# Backplane_Breakout_Adapter_Connectors.net
KiCad netlist of a schematic drawn in Altium Designer
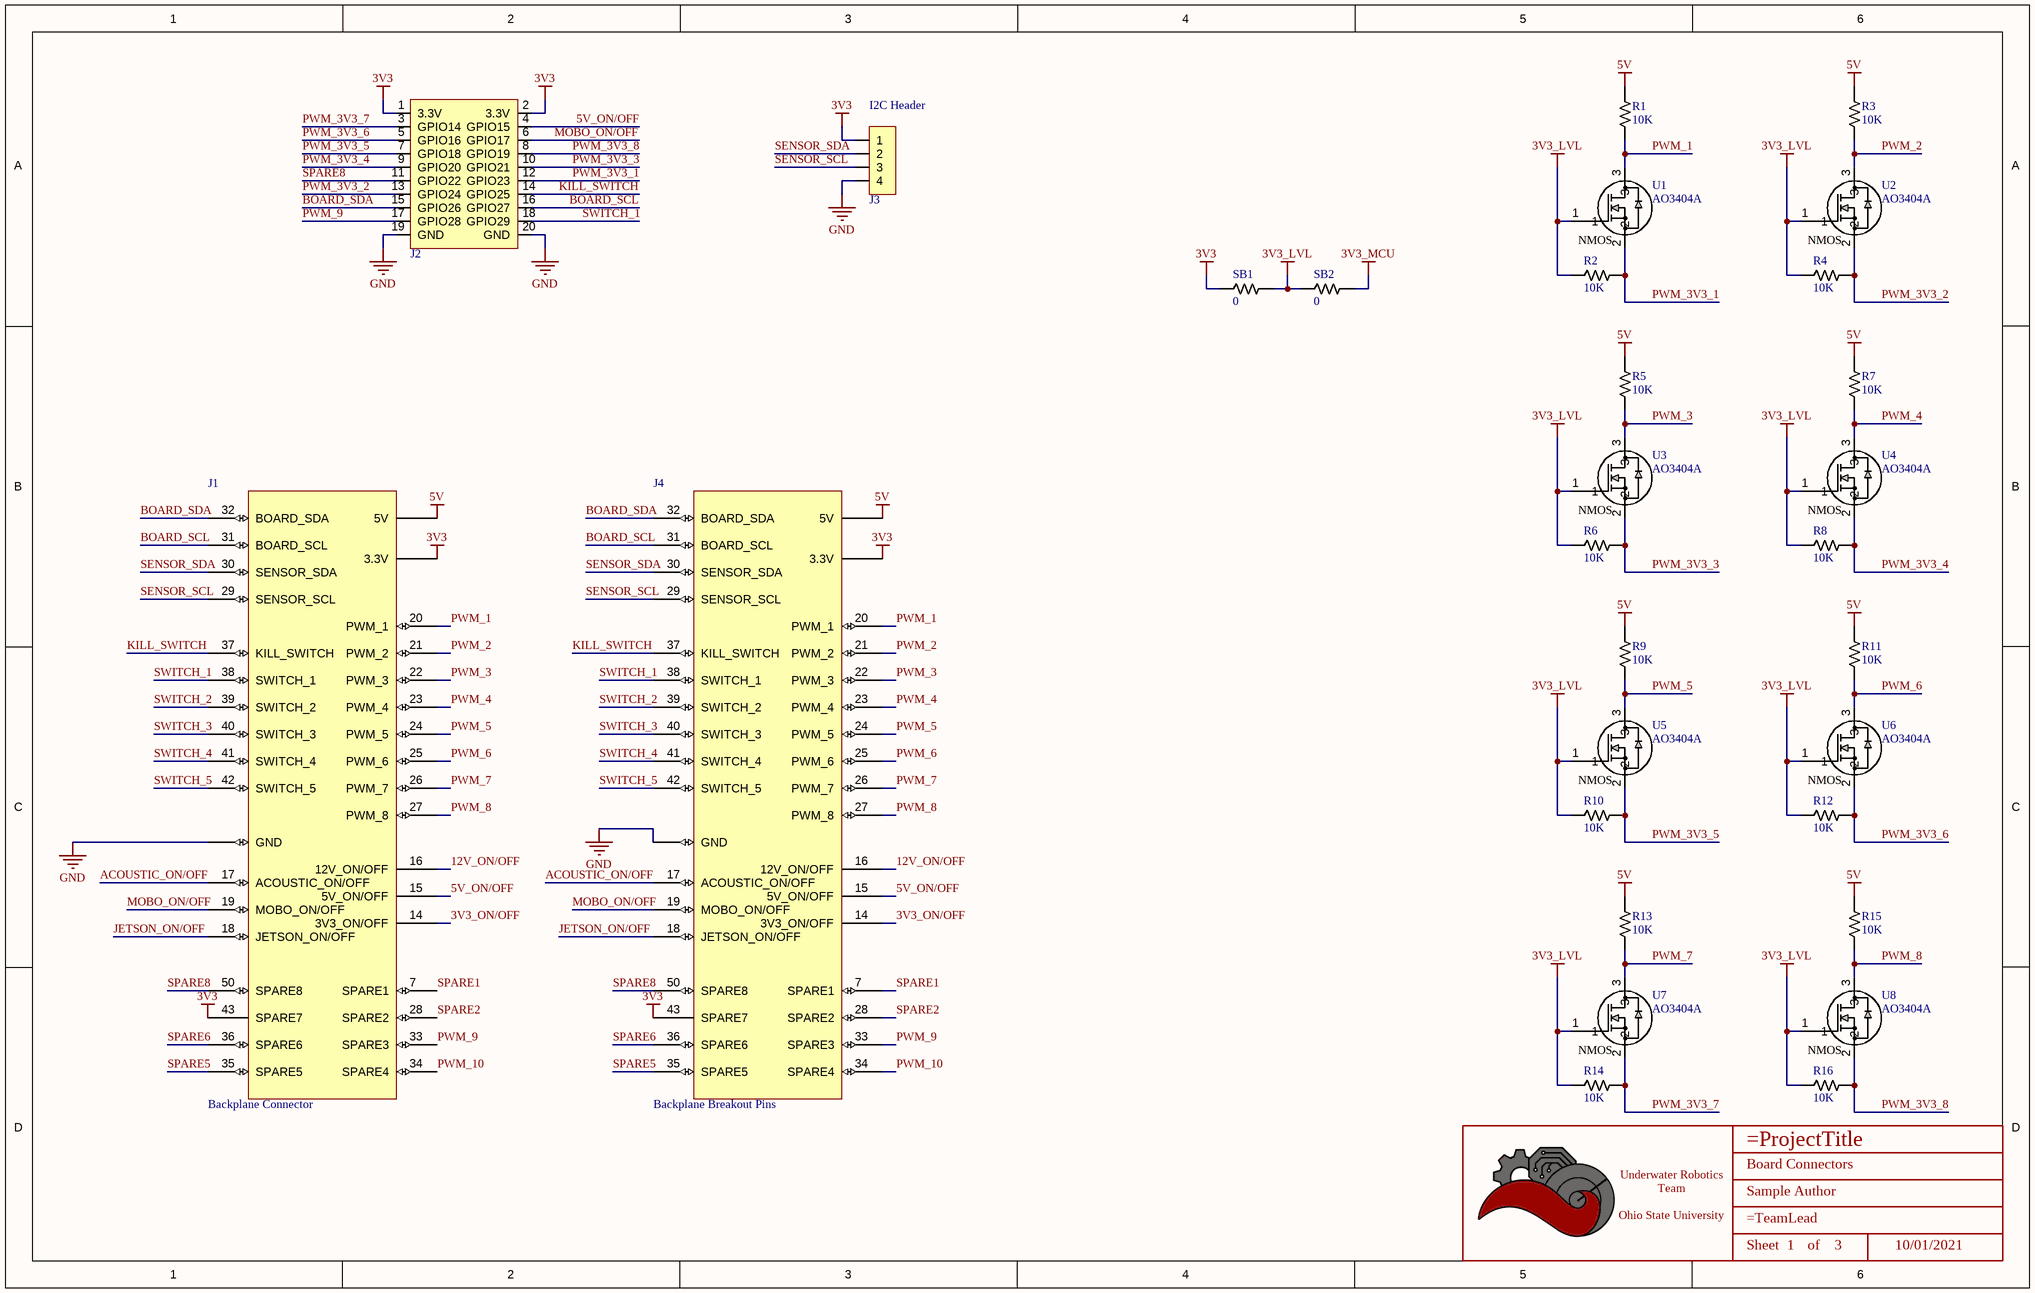
[diagram p0: Backplane_Breakout_Adapter_Connectors.SchDoc]

(export (version "E")
  (design (tool "Eeschema 10.0.6"))
  (components
    (comp (ref "*")
      (value "Title_Block")
      (footprint "LOGO")
      (description "UWRT Schematic Title Block Template\r\n\r\nCreated June 2021, Dylan Trainor")
      (libsource (lib "UWRT") (part "Title_Block"))
    )
    (comp (ref "J1")
      (value "Backplane Connector")
      (footprint "BACKPLANE_EDGE_CONN")
      (description "Titan Backplane Edge Connector")
      (libsource (lib "Connectors") (part "BACKBOARD_EDGE_CONN"))
    )
    (comp (ref "J2")
      (value "RP2040 GPIO Header")
      (footprint "HEADER_MIRRORED_2x10PIN_2.54MM")
      (description "CONN HEADER VERT 20POS 2.54MM")
      (fields (field (name "MADE BY") "Robert Pafford"))
      (libsource (lib "Connectors") (part "HEADER_2x10PIN_2.54MM_RP2040_GPIO"))
    )
    (comp (ref "J3")
      (value "CONN HEADER VERT 4POS 2.54MM")
      (footprint "HEADER_MIRRORED_4PIN_2.54MM")
      (fields (field (name "MADE BY") "Robert Pafford"))
      (libsource (lib "Connectors") (part "HEADER_4PIN_2.54MM"))
    )
    (comp (ref "J4")
      (value "Backplane Breakout Pins")
      (footprint "HEADER_2X28PIN_2.54MM")
      (description "Titan Backplane Edge Connector")
      (libsource (lib "Connectors") (part "BACKBOARD_EDGE_CONN"))
    )
    (comp (ref "R1")
      (value "10k Ohm 5% 1/10W")
      (footprint "RESISTOR_0603")
      (description "RES 10k OHM 5% 1/10W 0603")
      (fields
        (field (name "TOLERANCE") "+/- 5%")
        (field (name "VALUE  (OHMS)") "10K")
        (field (name "MADE BY") "Robert Pafford")
      )
      (libsource (lib "Resistors") (part "RESISTOR_10K_0603"))
    )
    (comp (ref "R2")
      (value "10k Ohm 5% 1/10W")
      (footprint "RESISTOR_0603")
      (description "RES 10k OHM 5% 1/10W 0603")
      (fields
        (field (name "TOLERANCE") "+/- 5%")
        (field (name "VALUE  (OHMS)") "10K")
        (field (name "MADE BY") "Robert Pafford")
      )
      (libsource (lib "Resistors") (part "RESISTOR_10K_0603"))
    )
    (comp (ref "R3")
      (value "10k Ohm 5% 1/10W")
      (footprint "RESISTOR_0603")
      (description "RES 10k OHM 5% 1/10W 0603")
      (fields
        (field (name "TOLERANCE") "+/- 5%")
        (field (name "VALUE  (OHMS)") "10K")
        (field (name "MADE BY") "Robert Pafford")
      )
      (libsource (lib "Resistors") (part "RESISTOR_10K_0603"))
    )
    (comp (ref "R4")
      (value "10k Ohm 5% 1/10W")
      (footprint "RESISTOR_0603")
      (description "RES 10k OHM 5% 1/10W 0603")
      (fields
        (field (name "TOLERANCE") "+/- 5%")
        (field (name "VALUE  (OHMS)") "10K")
        (field (name "MADE BY") "Robert Pafford")
      )
      (libsource (lib "Resistors") (part "RESISTOR_10K_0603"))
    )
    (comp (ref "R5")
      (value "10k Ohm 5% 1/10W")
      (footprint "RESISTOR_0603")
      (description "RES 10k OHM 5% 1/10W 0603")
      (fields
        (field (name "TOLERANCE") "+/- 5%")
        (field (name "VALUE  (OHMS)") "10K")
        (field (name "MADE BY") "Robert Pafford")
      )
      (libsource (lib "Resistors") (part "RESISTOR_10K_0603"))
    )
    (comp (ref "R6")
      (value "10k Ohm 5% 1/10W")
      (footprint "RESISTOR_0603")
      (description "RES 10k OHM 5% 1/10W 0603")
      (fields
        (field (name "TOLERANCE") "+/- 5%")
        (field (name "VALUE  (OHMS)") "10K")
        (field (name "MADE BY") "Robert Pafford")
      )
      (libsource (lib "Resistors") (part "RESISTOR_10K_0603"))
    )
    (comp (ref "R7")
      (value "10k Ohm 5% 1/10W")
      (footprint "RESISTOR_0603")
      (description "RES 10k OHM 5% 1/10W 0603")
      (fields
        (field (name "TOLERANCE") "+/- 5%")
        (field (name "VALUE  (OHMS)") "10K")
        (field (name "MADE BY") "Robert Pafford")
      )
      (libsource (lib "Resistors") (part "RESISTOR_10K_0603"))
    )
    (comp (ref "R8")
      (value "10k Ohm 5% 1/10W")
      (footprint "RESISTOR_0603")
      (description "RES 10k OHM 5% 1/10W 0603")
      (fields
        (field (name "TOLERANCE") "+/- 5%")
        (field (name "VALUE  (OHMS)") "10K")
        (field (name "MADE BY") "Robert Pafford")
      )
      (libsource (lib "Resistors") (part "RESISTOR_10K_0603"))
    )
    (comp (ref "R9")
      (value "10k Ohm 5% 1/10W")
      (footprint "RESISTOR_0603")
      (description "RES 10k OHM 5% 1/10W 0603")
      (fields
        (field (name "TOLERANCE") "+/- 5%")
        (field (name "VALUE  (OHMS)") "10K")
        (field (name "MADE BY") "Robert Pafford")
      )
      (libsource (lib "Resistors") (part "RESISTOR_10K_0603"))
    )
    (comp (ref "R10")
      (value "10k Ohm 5% 1/10W")
      (footprint "RESISTOR_0603")
      (description "RES 10k OHM 5% 1/10W 0603")
      (fields
        (field (name "TOLERANCE") "+/- 5%")
        (field (name "VALUE  (OHMS)") "10K")
        (field (name "MADE BY") "Robert Pafford")
      )
      (libsource (lib "Resistors") (part "RESISTOR_10K_0603"))
    )
    (comp (ref "R11")
      (value "10k Ohm 5% 1/10W")
      (footprint "RESISTOR_0603")
      (description "RES 10k OHM 5% 1/10W 0603")
      (fields
        (field (name "TOLERANCE") "+/- 5%")
        (field (name "VALUE  (OHMS)") "10K")
        (field (name "MADE BY") "Robert Pafford")
      )
      (libsource (lib "Resistors") (part "RESISTOR_10K_0603"))
    )
    (comp (ref "R12")
      (value "10k Ohm 5% 1/10W")
      (footprint "RESISTOR_0603")
      (description "RES 10k OHM 5% 1/10W 0603")
      (fields
        (field (name "TOLERANCE") "+/- 5%")
        (field (name "VALUE  (OHMS)") "10K")
        (field (name "MADE BY") "Robert Pafford")
      )
      (libsource (lib "Resistors") (part "RESISTOR_10K_0603"))
    )
    (comp (ref "R13")
      (value "10k Ohm 5% 1/10W")
      (footprint "RESISTOR_0603")
      (description "RES 10k OHM 5% 1/10W 0603")
      (fields
        (field (name "TOLERANCE") "+/- 5%")
        (field (name "VALUE  (OHMS)") "10K")
        (field (name "MADE BY") "Robert Pafford")
      )
      (libsource (lib "Resistors") (part "RESISTOR_10K_0603"))
    )
    (comp (ref "R14")
      (value "10k Ohm 5% 1/10W")
      (footprint "RESISTOR_0603")
      (description "RES 10k OHM 5% 1/10W 0603")
      (fields
        (field (name "TOLERANCE") "+/- 5%")
        (field (name "VALUE  (OHMS)") "10K")
        (field (name "MADE BY") "Robert Pafford")
      )
      (libsource (lib "Resistors") (part "RESISTOR_10K_0603"))
    )
    (comp (ref "R15")
      (value "10k Ohm 5% 1/10W")
      (footprint "RESISTOR_0603")
      (description "RES 10k OHM 5% 1/10W 0603")
      (fields
        (field (name "TOLERANCE") "+/- 5%")
        (field (name "VALUE  (OHMS)") "10K")
        (field (name "MADE BY") "Robert Pafford")
      )
      (libsource (lib "Resistors") (part "RESISTOR_10K_0603"))
    )
    (comp (ref "R16")
      (value "10k Ohm 5% 1/10W")
      (footprint "RESISTOR_0603")
      (description "RES 10k OHM 5% 1/10W 0603")
      (fields
        (field (name "TOLERANCE") "+/- 5%")
        (field (name "VALUE  (OHMS)") "10K")
        (field (name "MADE BY") "Robert Pafford")
      )
      (libsource (lib "Resistors") (part "RESISTOR_10K_0603"))
    )
    (comp (ref "SB1")
      (value "0 Ohm Jumper No Fit")
      (footprint "RESISTOR_0603")
      (description "0 Ohm Jumper No Fit for Solder Bridge")
      (fields (field (name "VALUE  (OHMS)") "0") (field (name "MADE BY") "Robert Pafford"))
      (libsource (lib "Resistors") (part "JUMPER_0_0603"))
    )
    (comp (ref "SB2")
      (value "0 Ohm Jumper No Fit")
      (footprint "RESISTOR_0603")
      (description "0 Ohm Jumper No Fit for Solder Bridge")
      (fields (field (name "VALUE  (OHMS)") "0") (field (name "MADE BY") "Robert Pafford"))
      (libsource (lib "Resistors") (part "JUMPER_0_0603"))
    )
    (comp (ref "U1")
      (value "AO3404A")
      (footprint "SOT-23-3")
      (description "N-Channel 30 V 5.8A (Ta) 1.4W (Ta) Surface Mount SOT-23-3")
      (fields (field (name "CREATED BY") "Dylan T"))
      (libsource (lib "Transistors") (part "AO3404A"))
    )
    (comp (ref "U2")
      (value "AO3404A")
      (footprint "SOT-23-3")
      (description "N-Channel 30 V 5.8A (Ta) 1.4W (Ta) Surface Mount SOT-23-3")
      (fields (field (name "CREATED BY") "Dylan T"))
      (libsource (lib "Transistors") (part "AO3404A"))
    )
    (comp (ref "U3")
      (value "AO3404A")
      (footprint "SOT-23-3")
      (description "N-Channel 30 V 5.8A (Ta) 1.4W (Ta) Surface Mount SOT-23-3")
      (fields (field (name "CREATED BY") "Dylan T"))
      (libsource (lib "Transistors") (part "AO3404A"))
    )
    (comp (ref "U4")
      (value "AO3404A")
      (footprint "SOT-23-3")
      (description "N-Channel 30 V 5.8A (Ta) 1.4W (Ta) Surface Mount SOT-23-3")
      (fields (field (name "CREATED BY") "Dylan T"))
      (libsource (lib "Transistors") (part "AO3404A"))
    )
    (comp (ref "U5")
      (value "AO3404A")
      (footprint "SOT-23-3")
      (description "N-Channel 30 V 5.8A (Ta) 1.4W (Ta) Surface Mount SOT-23-3")
      (fields (field (name "CREATED BY") "Dylan T"))
      (libsource (lib "Transistors") (part "AO3404A"))
    )
    (comp (ref "U6")
      (value "AO3404A")
      (footprint "SOT-23-3")
      (description "N-Channel 30 V 5.8A (Ta) 1.4W (Ta) Surface Mount SOT-23-3")
      (fields (field (name "CREATED BY") "Dylan T"))
      (libsource (lib "Transistors") (part "AO3404A"))
    )
    (comp (ref "U7")
      (value "AO3404A")
      (footprint "SOT-23-3")
      (description "N-Channel 30 V 5.8A (Ta) 1.4W (Ta) Surface Mount SOT-23-3")
      (fields (field (name "CREATED BY") "Dylan T"))
      (libsource (lib "Transistors") (part "AO3404A"))
    )
    (comp (ref "U8")
      (value "AO3404A")
      (footprint "SOT-23-3")
      (description "N-Channel 30 V 5.8A (Ta) 1.4W (Ta) Surface Mount SOT-23-3")
      (fields (field (name "CREATED BY") "Dylan T"))
      (libsource (lib "Transistors") (part "AO3404A"))
    )
  )
  (nets
    (net (code "1") (name "/3V3_ON{slash}OFF") (class "Default")
      (node (ref "J1") (pin "14") (pinfunction "3V3_ON/OFF_14") (pintype "power_in"))
      (node (ref "J4") (pin "14") (pinfunction "3V3_ON/OFF_14") (pintype "power_in"))
    )
    (net (code "2") (name "/5V_ON{slash}OFF") (class "Default")
      (node (ref "J1") (pin "15") (pinfunction "5V_ON/OFF_15") (pintype "power_in"))
      (node (ref "J2") (pin "4") (pinfunction "GPIO15_4") (pintype "bidirectional"))
      (node (ref "J4") (pin "15") (pinfunction "5V_ON/OFF_15") (pintype "power_in"))
    )
    (net (code "3") (name "/12V_ON{slash}OFF") (class "Default")
      (node (ref "J1") (pin "16") (pinfunction "12V_ON/OFF_16") (pintype "power_in"))
      (node (ref "J4") (pin "16") (pinfunction "12V_ON/OFF_16") (pintype "power_in"))
    )
    (net (code "4") (name "/ACOUSTIC_ON{slash}OFF") (class "Default")
      (node (ref "J1") (pin "17") (pinfunction "ACOUSTIC_ON/OFF_17") (pintype "bidirectional"))
      (node (ref "J4") (pin "17") (pinfunction "ACOUSTIC_ON/OFF_17") (pintype "bidirectional"))
    )
    (net (code "5") (name "/BOARD_SCL") (class "Default")
      (node (ref "J1") (pin "31") (pinfunction "BOARD_SCL_31") (pintype "bidirectional"))
      (node (ref "J2") (pin "16") (pinfunction "GPIO27_16") (pintype "bidirectional"))
      (node (ref "J4") (pin "31") (pinfunction "BOARD_SCL_31") (pintype "bidirectional"))
    )
    (net (code "6") (name "/BOARD_SDA") (class "Default")
      (node (ref "J1") (pin "32") (pinfunction "BOARD_SDA_32") (pintype "bidirectional"))
      (node (ref "J2") (pin "15") (pinfunction "GPIO26_15") (pintype "bidirectional"))
      (node (ref "J4") (pin "32") (pinfunction "BOARD_SDA_32") (pintype "bidirectional"))
    )
    (net (code "7") (name "/JETSON_ON{slash}OFF") (class "Default")
      (node (ref "J1") (pin "18") (pinfunction "JETSON_ON/OFF_18") (pintype "bidirectional"))
      (node (ref "J4") (pin "18") (pinfunction "JETSON_ON/OFF_18") (pintype "bidirectional"))
    )
    (net (code "8") (name "/KILL_SWITCH") (class "Default")
      (node (ref "J1") (pin "37") (pinfunction "KILL_SWITCH_37") (pintype "bidirectional"))
      (node (ref "J2") (pin "14") (pinfunction "GPIO25_14") (pintype "bidirectional"))
      (node (ref "J4") (pin "37") (pinfunction "KILL_SWITCH_37") (pintype "bidirectional"))
    )
    (net (code "9") (name "/MOBO_ON{slash}OFF") (class "Default")
      (node (ref "J1") (pin "19") (pinfunction "MOBO_ON/OFF_19") (pintype "bidirectional"))
      (node (ref "J2") (pin "6") (pinfunction "GPIO17_6") (pintype "bidirectional"))
      (node (ref "J4") (pin "19") (pinfunction "MOBO_ON/OFF_19") (pintype "bidirectional"))
    )
    (net (code "10") (name "/PWM_1") (class "Default")
      (node (ref "J1") (pin "20") (pinfunction "PWM_1_20") (pintype "bidirectional"))
      (node (ref "J4") (pin "20") (pinfunction "PWM_1_20") (pintype "bidirectional"))
      (node (ref "R1") (pin "2") (pinfunction "2_2") (pintype "passive"))
      (node (ref "U1") (pin "3") (pinfunction "3_3") (pintype "passive"))
    )
    (net (code "11") (name "/PWM_2") (class "Default")
      (node (ref "J1") (pin "21") (pinfunction "PWM_2_21") (pintype "bidirectional"))
      (node (ref "J4") (pin "21") (pinfunction "PWM_2_21") (pintype "bidirectional"))
      (node (ref "R3") (pin "2") (pinfunction "2_2") (pintype "passive"))
      (node (ref "U2") (pin "3") (pinfunction "3_3") (pintype "passive"))
    )
    (net (code "12") (name "/PWM_3") (class "Default")
      (node (ref "J1") (pin "22") (pinfunction "PWM_3_22") (pintype "bidirectional"))
      (node (ref "J4") (pin "22") (pinfunction "PWM_3_22") (pintype "bidirectional"))
      (node (ref "R5") (pin "2") (pinfunction "2_2") (pintype "passive"))
      (node (ref "U3") (pin "3") (pinfunction "3_3") (pintype "passive"))
    )
    (net (code "13") (name "/PWM_3V3_1") (class "Default")
      (node (ref "J2") (pin "12") (pinfunction "GPIO23_12") (pintype "bidirectional"))
      (node (ref "R2") (pin "1") (pinfunction "1_1") (pintype "passive"))
      (node (ref "U1") (pin "2") (pinfunction "2_2") (pintype "passive"))
    )
    (net (code "14") (name "/PWM_3V3_2") (class "Default")
      (node (ref "J2") (pin "13") (pinfunction "GPIO24_13") (pintype "bidirectional"))
      (node (ref "R4") (pin "1") (pinfunction "1_1") (pintype "passive"))
      (node (ref "U2") (pin "2") (pinfunction "2_2") (pintype "passive"))
    )
    (net (code "15") (name "/PWM_3V3_3") (class "Default")
      (node (ref "J2") (pin "10") (pinfunction "GPIO21_10") (pintype "bidirectional"))
      (node (ref "R6") (pin "1") (pinfunction "1_1") (pintype "passive"))
      (node (ref "U3") (pin "2") (pinfunction "2_2") (pintype "passive"))
    )
    (net (code "16") (name "/PWM_3V3_4") (class "Default")
      (node (ref "J2") (pin "9") (pinfunction "GPIO20_9") (pintype "bidirectional"))
      (node (ref "R8") (pin "1") (pinfunction "1_1") (pintype "passive"))
      (node (ref "U4") (pin "2") (pinfunction "2_2") (pintype "passive"))
    )
    (net (code "17") (name "/PWM_3V3_5") (class "Default")
      (node (ref "J2") (pin "7") (pinfunction "GPIO18_7") (pintype "bidirectional"))
      (node (ref "R10") (pin "1") (pinfunction "1_1") (pintype "passive"))
      (node (ref "U5") (pin "2") (pinfunction "2_2") (pintype "passive"))
    )
    (net (code "18") (name "/PWM_3V3_6") (class "Default")
      (node (ref "J2") (pin "5") (pinfunction "GPIO16_5") (pintype "bidirectional"))
      (node (ref "R12") (pin "1") (pinfunction "1_1") (pintype "passive"))
      (node (ref "U6") (pin "2") (pinfunction "2_2") (pintype "passive"))
    )
    (net (code "19") (name "/PWM_3V3_7") (class "Default")
      (node (ref "J2") (pin "3") (pinfunction "GPIO14_3") (pintype "bidirectional"))
      (node (ref "R14") (pin "1") (pinfunction "1_1") (pintype "passive"))
      (node (ref "U7") (pin "2") (pinfunction "2_2") (pintype "passive"))
    )
    (net (code "20") (name "/PWM_3V3_8") (class "Default")
      (node (ref "J2") (pin "8") (pinfunction "GPIO19_8") (pintype "bidirectional"))
      (node (ref "R16") (pin "1") (pinfunction "1_1") (pintype "passive"))
      (node (ref "U8") (pin "2") (pinfunction "2_2") (pintype "passive"))
    )
    (net (code "21") (name "/PWM_4") (class "Default")
      (node (ref "J1") (pin "23") (pinfunction "PWM_4_23") (pintype "bidirectional"))
      (node (ref "J4") (pin "23") (pinfunction "PWM_4_23") (pintype "bidirectional"))
      (node (ref "R7") (pin "2") (pinfunction "2_2") (pintype "passive"))
      (node (ref "U4") (pin "3") (pinfunction "3_3") (pintype "passive"))
    )
    (net (code "22") (name "/PWM_5") (class "Default")
      (node (ref "J1") (pin "24") (pinfunction "PWM_5_24") (pintype "bidirectional"))
      (node (ref "J4") (pin "24") (pinfunction "PWM_5_24") (pintype "bidirectional"))
      (node (ref "R9") (pin "2") (pinfunction "2_2") (pintype "passive"))
      (node (ref "U5") (pin "3") (pinfunction "3_3") (pintype "passive"))
    )
    (net (code "23") (name "/PWM_6") (class "Default")
      (node (ref "J1") (pin "25") (pinfunction "PWM_6_25") (pintype "bidirectional"))
      (node (ref "J4") (pin "25") (pinfunction "PWM_6_25") (pintype "bidirectional"))
      (node (ref "R11") (pin "2") (pinfunction "2_2") (pintype "passive"))
      (node (ref "U6") (pin "3") (pinfunction "3_3") (pintype "passive"))
    )
    (net (code "24") (name "/PWM_7") (class "Default")
      (node (ref "J1") (pin "26") (pinfunction "PWM_7_26") (pintype "bidirectional"))
      (node (ref "J4") (pin "26") (pinfunction "PWM_7_26") (pintype "bidirectional"))
      (node (ref "R13") (pin "2") (pinfunction "2_2") (pintype "passive"))
      (node (ref "U7") (pin "3") (pinfunction "3_3") (pintype "passive"))
    )
    (net (code "25") (name "/PWM_8") (class "Default")
      (node (ref "J1") (pin "27") (pinfunction "PWM_8_27") (pintype "bidirectional"))
      (node (ref "J4") (pin "27") (pinfunction "PWM_8_27") (pintype "bidirectional"))
      (node (ref "R15") (pin "2") (pinfunction "2_2") (pintype "passive"))
      (node (ref "U8") (pin "3") (pinfunction "3_3") (pintype "passive"))
    )
    (net (code "26") (name "/PWM_9") (class "Default")
      (node (ref "J1") (pin "33") (pinfunction "SPARE3_33") (pintype "bidirectional"))
      (node (ref "J2") (pin "17") (pinfunction "GPIO28_17") (pintype "bidirectional"))
      (node (ref "J4") (pin "33") (pinfunction "SPARE3_33") (pintype "bidirectional"))
    )
    (net (code "27") (name "/PWM_10") (class "Default")
      (node (ref "J1") (pin "34") (pinfunction "SPARE4_34") (pintype "bidirectional"))
      (node (ref "J4") (pin "34") (pinfunction "SPARE4_34") (pintype "bidirectional"))
    )
    (net (code "28") (name "/SENSOR_SCL") (class "Default")
      (node (ref "J1") (pin "29") (pinfunction "SENSOR_SCL_29") (pintype "bidirectional"))
      (node (ref "J3") (pin "3") (pinfunction "3_3") (pintype "passive"))
      (node (ref "J4") (pin "29") (pinfunction "SENSOR_SCL_29") (pintype "bidirectional"))
    )
    (net (code "29") (name "/SENSOR_SDA") (class "Default")
      (node (ref "J1") (pin "30") (pinfunction "SENSOR_SDA_30") (pintype "bidirectional"))
      (node (ref "J3") (pin "2") (pinfunction "2_2") (pintype "passive"))
      (node (ref "J4") (pin "30") (pinfunction "SENSOR_SDA_30") (pintype "bidirectional"))
    )
    (net (code "30") (name "/SPARE1") (class "Default")
      (node (ref "J1") (pin "7") (pinfunction "SPARE1_7") (pintype "bidirectional"))
      (node (ref "J4") (pin "7") (pinfunction "SPARE1_7") (pintype "bidirectional"))
    )
    (net (code "31") (name "/SPARE2") (class "Default")
      (node (ref "J1") (pin "28") (pinfunction "SPARE2_28") (pintype "bidirectional"))
      (node (ref "J4") (pin "28") (pinfunction "SPARE2_28") (pintype "bidirectional"))
    )
    (net (code "32") (name "/SPARE5") (class "Default")
      (node (ref "J1") (pin "35") (pinfunction "SPARE5_35") (pintype "bidirectional"))
      (node (ref "J4") (pin "35") (pinfunction "SPARE5_35") (pintype "bidirectional"))
    )
    (net (code "33") (name "/SPARE6") (class "Default")
      (node (ref "J1") (pin "36") (pinfunction "SPARE6_36") (pintype "bidirectional"))
      (node (ref "J4") (pin "36") (pinfunction "SPARE6_36") (pintype "bidirectional"))
    )
    (net (code "34") (name "/SPARE8") (class "Default")
      (node (ref "J1") (pin "50") (pinfunction "SPARE8_50") (pintype "bidirectional"))
      (node (ref "J2") (pin "11") (pinfunction "GPIO22_11") (pintype "bidirectional"))
      (node (ref "J4") (pin "50") (pinfunction "SPARE8_50") (pintype "bidirectional"))
    )
    (net (code "35") (name "/SWITCH_1") (class "Default")
      (node (ref "J1") (pin "38") (pinfunction "SWITCH_1_38") (pintype "bidirectional"))
      (node (ref "J2") (pin "18") (pinfunction "GPIO29_18") (pintype "bidirectional"))
      (node (ref "J4") (pin "38") (pinfunction "SWITCH_1_38") (pintype "bidirectional"))
    )
    (net (code "36") (name "/SWITCH_2") (class "Default")
      (node (ref "J1") (pin "39") (pinfunction "SWITCH_2_39") (pintype "bidirectional"))
      (node (ref "J4") (pin "39") (pinfunction "SWITCH_2_39") (pintype "bidirectional"))
    )
    (net (code "37") (name "/SWITCH_3") (class "Default")
      (node (ref "J1") (pin "40") (pinfunction "SWITCH_3_40") (pintype "bidirectional"))
      (node (ref "J4") (pin "40") (pinfunction "SWITCH_3_40") (pintype "bidirectional"))
    )
    (net (code "38") (name "/SWITCH_4") (class "Default")
      (node (ref "J1") (pin "41") (pinfunction "SWITCH_4_41") (pintype "bidirectional"))
      (node (ref "J4") (pin "41") (pinfunction "SWITCH_4_41") (pintype "bidirectional"))
    )
    (net (code "39") (name "/SWITCH_5") (class "Default")
      (node (ref "J1") (pin "42") (pinfunction "SWITCH_5_42") (pintype "bidirectional"))
      (node (ref "J4") (pin "42") (pinfunction "SWITCH_5_42") (pintype "bidirectional"))
    )
    (net (code "40") (name "3V3") (class "Default")
      (node (ref "J1") (pin "1*6") (pinfunction "3.3V_1*6") (pintype "power_in"))
      (node (ref "J1") (pin "43") (pinfunction "SPARE7_43") (pintype "power_in"))
      (node (ref "J2") (pin "1") (pinfunction "3.3V_1") (pintype "power_in"))
      (node (ref "J2") (pin "2") (pinfunction "3.3V_2") (pintype "power_in"))
      (node (ref "J3") (pin "1") (pinfunction "1_1") (pintype "passive"))
      (node (ref "J4") (pin "1*6") (pinfunction "3.3V_1*6") (pintype "power_in"))
      (node (ref "J4") (pin "43") (pinfunction "SPARE7_43") (pintype "power_in"))
      (node (ref "SB1") (pin "2") (pinfunction "2_2") (pintype "passive"))
    )
    (net (code "41") (name "3V3_LVL") (class "Default")
      (node (ref "R10") (pin "2") (pinfunction "2_2") (pintype "passive"))
      (node (ref "R12") (pin "2") (pinfunction "2_2") (pintype "passive"))
      (node (ref "R14") (pin "2") (pinfunction "2_2") (pintype "passive"))
      (node (ref "R16") (pin "2") (pinfunction "2_2") (pintype "passive"))
      (node (ref "R2") (pin "2") (pinfunction "2_2") (pintype "passive"))
      (node (ref "R4") (pin "2") (pinfunction "2_2") (pintype "passive"))
      (node (ref "R6") (pin "2") (pinfunction "2_2") (pintype "passive"))
      (node (ref "R8") (pin "2") (pinfunction "2_2") (pintype "passive"))
      (node (ref "SB1") (pin "1") (pinfunction "1_1") (pintype "passive"))
      (node (ref "SB2") (pin "2") (pinfunction "2_2") (pintype "passive"))
      (node (ref "U1") (pin "1") (pinfunction "1_1") (pintype "passive"))
      (node (ref "U2") (pin "1") (pinfunction "1_1") (pintype "passive"))
      (node (ref "U3") (pin "1") (pinfunction "1_1") (pintype "passive"))
      (node (ref "U4") (pin "1") (pinfunction "1_1") (pintype "passive"))
      (node (ref "U5") (pin "1") (pinfunction "1_1") (pintype "passive"))
      (node (ref "U6") (pin "1") (pinfunction "1_1") (pintype "passive"))
      (node (ref "U7") (pin "1") (pinfunction "1_1") (pintype "passive"))
      (node (ref "U8") (pin "1") (pinfunction "1_1") (pintype "passive"))
    )
    (net (code "42") (name "3V3_MCU") (class "Default")
      (node (ref "SB2") (pin "1") (pinfunction "1_1") (pintype "passive"))
    )
    (net (code "43") (name "5V") (class "Default")
      (node (ref "J1") (pin "11*6") (pinfunction "5V_11*6") (pintype "power_in"))
      (node (ref "J4") (pin "11*6") (pinfunction "5V_11*6") (pintype "power_in"))
      (node (ref "R1") (pin "1") (pinfunction "1_1") (pintype "passive"))
      (node (ref "R11") (pin "1") (pinfunction "1_1") (pintype "passive"))
      (node (ref "R13") (pin "1") (pinfunction "1_1") (pintype "passive"))
      (node (ref "R15") (pin "1") (pinfunction "1_1") (pintype "passive"))
      (node (ref "R3") (pin "1") (pinfunction "1_1") (pintype "passive"))
      (node (ref "R5") (pin "1") (pinfunction "1_1") (pintype "passive"))
      (node (ref "R7") (pin "1") (pinfunction "1_1") (pintype "passive"))
      (node (ref "R9") (pin "1") (pinfunction "1_1") (pintype "passive"))
    )
    (net (code "44") (name "GND") (class "Default")
      (node (ref "J1") (pin "4*12") (pinfunction "GND_4*12") (pintype "bidirectional"))
      (node (ref "J2") (pin "19") (pinfunction "GND_19") (pintype "power_in"))
      (node (ref "J2") (pin "20") (pinfunction "GND_20") (pintype "power_in"))
      (node (ref "J3") (pin "4") (pinfunction "4_4") (pintype "passive"))
      (node (ref "J4") (pin "4*12") (pinfunction "GND_4*12") (pintype "bidirectional"))
    )
  )
)
